# ptSolar.net
KiCad netlist of a schematic drawn in EAGLE
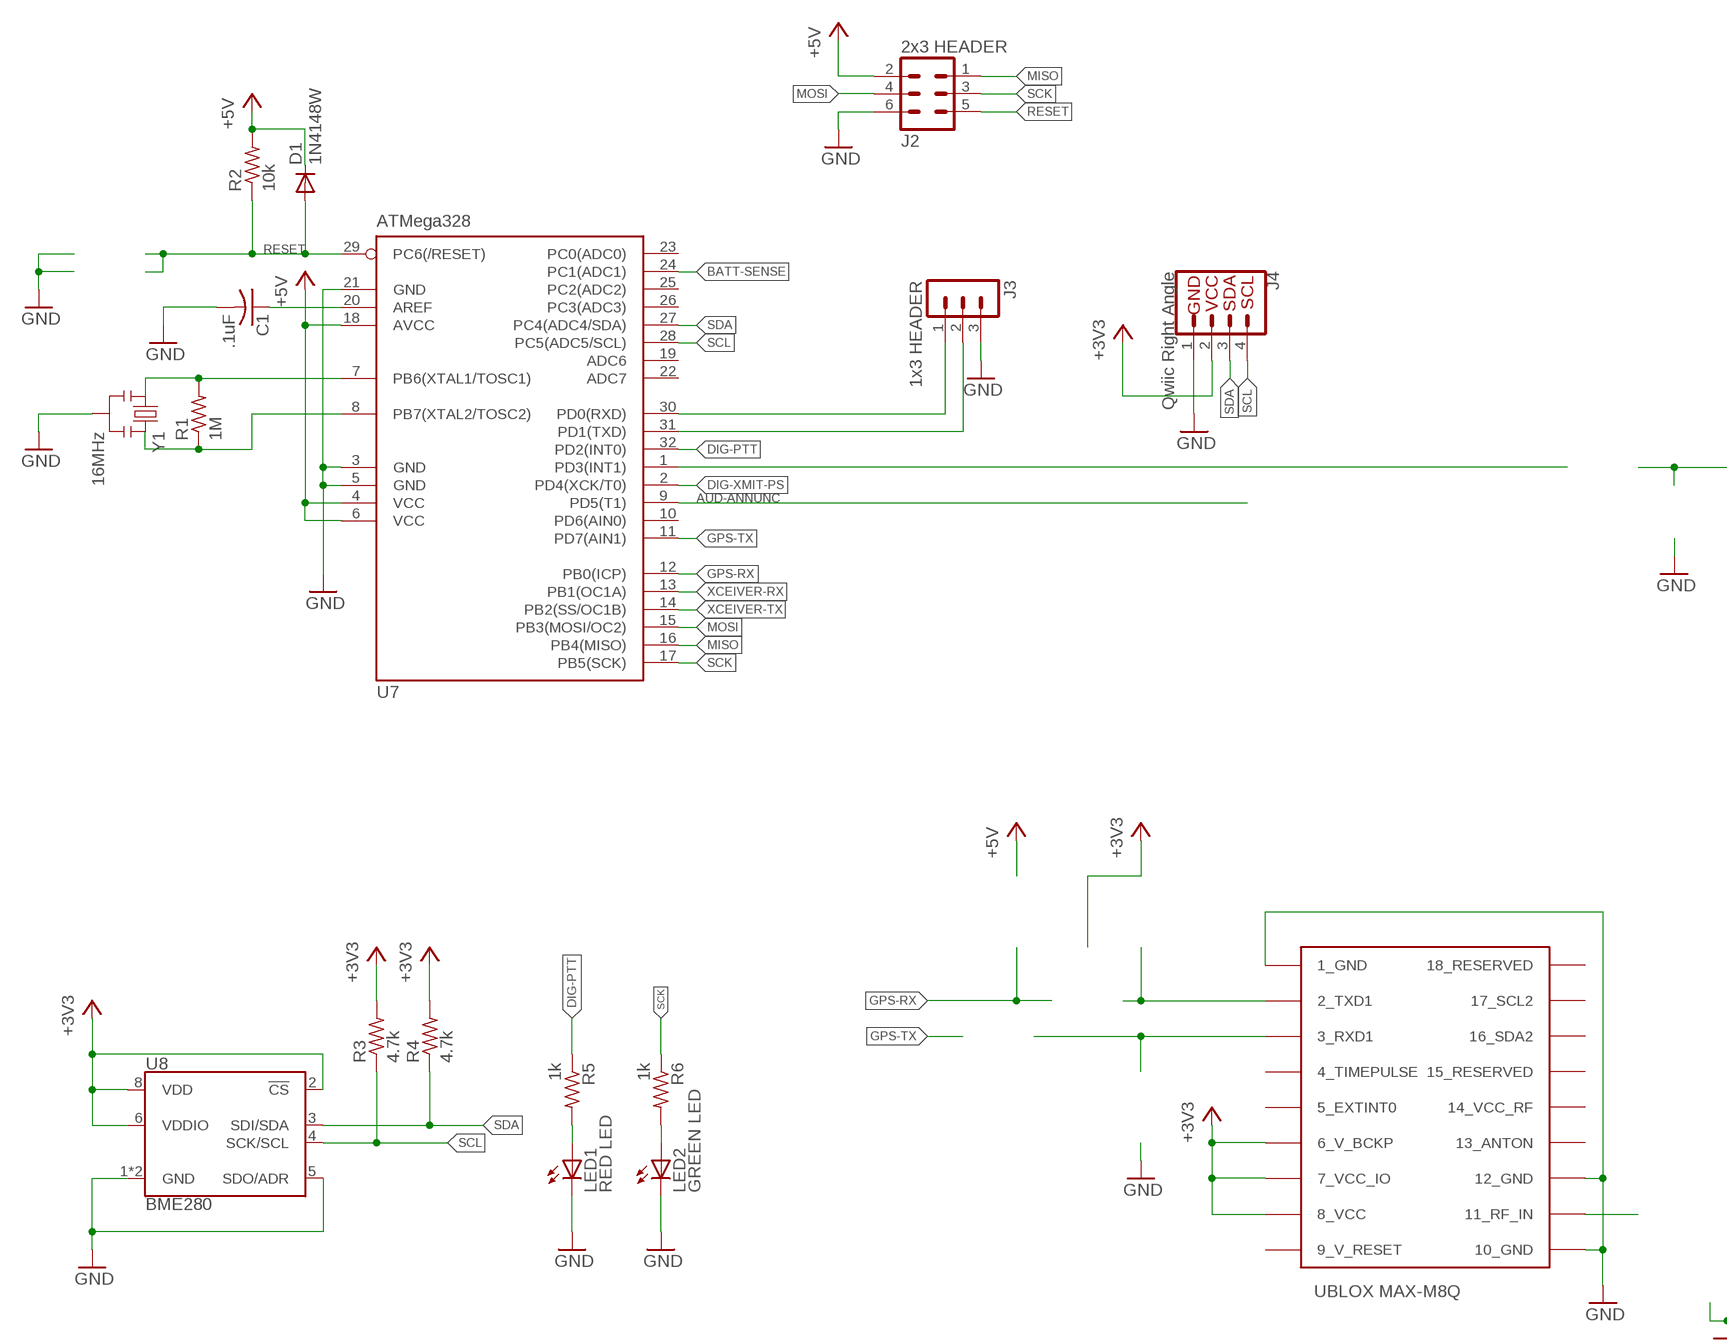
[diagram p0: schematic, sheet 1, part 1 of 2]
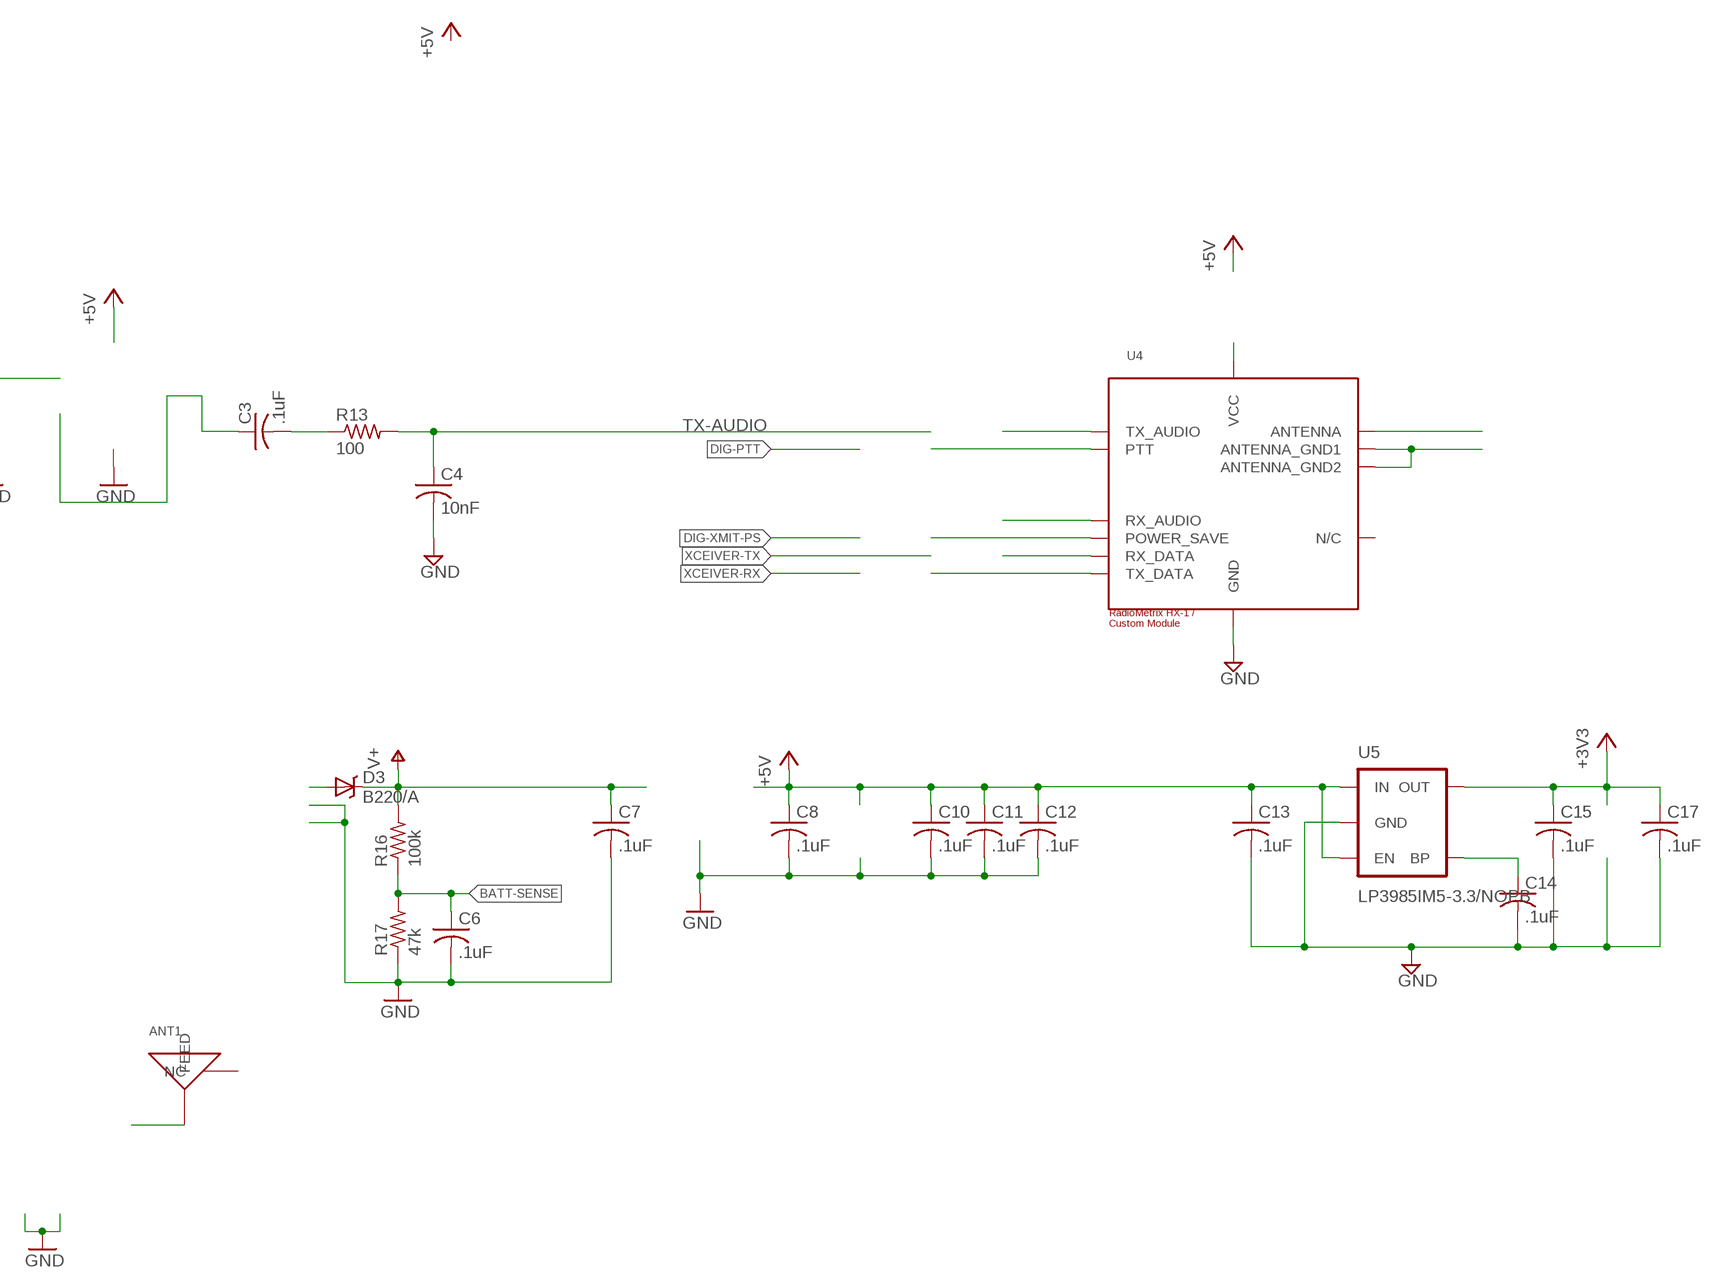
[diagram p1: schematic, sheet 1, part 2 of 2]

(export (version "E")
  (design (tool "Eeschema 10.0.6"))
  (components
    (comp (ref "ANT1")
      (value "GPS ANTENNA")
      (footprint "eagle-import:1575AT43A40")
      (libsource (lib "eagle-import") (part "GPS_ANT_SMDBAR"))
    )
    (comp (ref "C1")
      (value ".1uF")
      (footprint "eagle-import:C0805")
      (libsource (lib "eagle-import") (part "C-USC0805"))
    )
    (comp (ref "C3")
      (value ".1uF")
      (footprint "eagle-import:C0805")
      (libsource (lib "eagle-import") (part "C-USC0805"))
    )
    (comp (ref "C4")
      (value "10nF")
      (footprint "eagle-import:C0805")
      (libsource (lib "eagle-import") (part "C-USC0805"))
    )
    (comp (ref "C6")
      (value ".1uF")
      (footprint "eagle-import:C0805")
      (libsource (lib "eagle-import") (part "C-USC0805"))
    )
    (comp (ref "C7")
      (value ".1uF")
      (footprint "eagle-import:C0805")
      (libsource (lib "eagle-import") (part "C-USC0805"))
    )
    (comp (ref "C8")
      (value ".1uF")
      (footprint "eagle-import:C0805")
      (libsource (lib "eagle-import") (part "C-USC0805"))
    )
    (comp (ref "C10")
      (value ".1uF")
      (footprint "eagle-import:C0805")
      (libsource (lib "eagle-import") (part "C-USC0805"))
    )
    (comp (ref "C11")
      (value ".1uF")
      (footprint "eagle-import:C0805")
      (libsource (lib "eagle-import") (part "C-USC0805"))
    )
    (comp (ref "C12")
      (value ".1uF")
      (footprint "eagle-import:C0805")
      (libsource (lib "eagle-import") (part "C-USC0805"))
    )
    (comp (ref "C13")
      (value ".1uF")
      (footprint "eagle-import:C0805")
      (libsource (lib "eagle-import") (part "C-USC0805"))
    )
    (comp (ref "C14")
      (value ".1uF")
      (footprint "eagle-import:C0805")
      (libsource (lib "eagle-import") (part "C-USC0805"))
    )
    (comp (ref "C15")
      (value ".1uF")
      (footprint "eagle-import:C0805")
      (libsource (lib "eagle-import") (part "C-USC0805"))
    )
    (comp (ref "C17")
      (value ".1uF")
      (footprint "eagle-import:C0805")
      (libsource (lib "eagle-import") (part "C-USC0805"))
    )
    (comp (ref "D1")
      (value "1N4148W")
      (footprint "eagle-import:SOD123")
      (libsource (lib "eagle-import") (part "DIODE-SOD123"))
    )
    (comp (ref "D3")
      (value "B220/A")
      (footprint "eagle-import:SMA-DIODE")
      (libsource (lib "eagle-import") (part "B340A"))
    )
    (comp (ref "J2")
      (value "2x3 HEADER")
      (footprint "eagle-import:MA03-2")
      (libsource (lib "eagle-import") (part "MA03-2"))
    )
    (comp (ref "J3")
      (value "1x3 HEADER")
      (footprint "eagle-import:MA03-1")
      (libsource (lib "eagle-import") (part "MA03-1"))
    )
    (comp (ref "J4")
      (value "Qwiic Right Angle")
      (footprint "eagle-import:1X04_1MM_RA")
      (libsource (lib "eagle-import") (part "I2C_STANDARDQWIIC"))
    )
    (comp (ref "LED1")
      (value "RED LED")
      (footprint "eagle-import:CHIPLED_1206")
      (libsource (lib "eagle-import") (part "LEDCHIPLED_1206"))
    )
    (comp (ref "LED2")
      (value "GREEN LED")
      (footprint "eagle-import:CHIPLED_1206")
      (libsource (lib "eagle-import") (part "LEDCHIPLED_1206"))
    )
    (comp (ref "R1")
      (value "1M")
      (footprint "eagle-import:R0805")
      (libsource (lib "eagle-import") (part "R-US_R0805"))
    )
    (comp (ref "R2")
      (value "10k")
      (footprint "eagle-import:R0805")
      (libsource (lib "eagle-import") (part "R-US_R0805"))
    )
    (comp (ref "R3")
      (value "4.7k")
      (footprint "eagle-import:R0805")
      (libsource (lib "eagle-import") (part "R-US_R0805"))
    )
    (comp (ref "R4")
      (value "4.7k")
      (footprint "eagle-import:R0805")
      (libsource (lib "eagle-import") (part "R-US_R0805"))
    )
    (comp (ref "R5")
      (value "1k")
      (footprint "eagle-import:R0805")
      (libsource (lib "eagle-import") (part "R-US_R0805"))
    )
    (comp (ref "R6")
      (value "1k")
      (footprint "eagle-import:R0805")
      (libsource (lib "eagle-import") (part "R-US_R0805"))
    )
    (comp (ref "R13")
      (value "100")
      (footprint "eagle-import:R0805")
      (libsource (lib "eagle-import") (part "R-US_R0805"))
    )
    (comp (ref "R16")
      (value "100k")
      (footprint "eagle-import:R0805")
      (libsource (lib "eagle-import") (part "R-US_R0805"))
    )
    (comp (ref "R17")
      (value "47k")
      (footprint "eagle-import:R0805")
      (libsource (lib "eagle-import") (part "R-US_R0805"))
    )
    (comp (ref "U2")
      (value "UBLOX_MAX")
      (footprint "eagle-import:UBLOX_MAX")
      (fields (field (name "ALT-PART") "UBLOX MAX-M8Q"))
      (libsource (lib "eagle-import") (part "UBLOX_MAX"))
    )
    (comp (ref "U4")
      (value "RADIOMETRIX-HX1-CUSTOM")
      (footprint "eagle-import:RADIOMETRIX-HX1-CUSTOM")
      (libsource (lib "eagle-import") (part "RADIOMETRIX-HX1-CUSTOM"))
    )
    (comp (ref "U5")
      (value "LP3985IM5-3.3/NOPB")
      (footprint "eagle-import:SOT23-5")
      (libsource (lib "eagle-import") (part "V_REG_LDOSMD"))
    )
    (comp (ref "U7")
      (value "ATMega328")
      (footprint "eagle-import:TQFP32-08")
      (fields (field (name "MPN") "ATMEGA8-16AU"))
      (libsource (lib "eagle-import") (part "MEGA8-AI"))
    )
    (comp (ref "U8")
      (value "BME280")
      (footprint "eagle-import:LGA-8-2.5X2.5")
      (libsource (lib "eagle-import") (part "BME280"))
    )
    (comp (ref "Y1")
      (value "16MHz")
      (footprint "eagle-import:RESONATOR-SMD")
      (libsource (lib "eagle-import") (part "RESONATOR16MHZ"))
    )
  )
  (nets
    (net (code "1") (name "+3V3") (class "Default")
      (node (ref "C15") (pin "1") (pinfunction "1_1") (pintype "passive"))
      (node (ref "C17") (pin "1") (pinfunction "1_1") (pintype "passive"))
      (node (ref "J4") (pin "2") (pinfunction "2_2") (pintype "power_in"))
      (node (ref "R3") (pin "2") (pinfunction "2_2") (pintype "passive"))
      (node (ref "R4") (pin "2") (pinfunction "2_2") (pintype "passive"))
      (node (ref "U2") (pin "6_V_BCKP") (pinfunction "6_V_BCKP_6_V_BCKP") (pintype "bidirectional"))
      (node (ref "U2") (pin "7_VCC_IO") (pinfunction "7_VCC_IO_7_VCC_IO") (pintype "power_in"))
      (node (ref "U2") (pin "8_VCC") (pinfunction "8_VCC_8_VCC") (pintype "power_in"))
      (node (ref "U5") (pin "5") (pinfunction "OUT_5") (pintype "passive"))
      (node (ref "U8") (pin "2") (pinfunction "~{CS}_2") (pintype "bidirectional"))
      (node (ref "U8") (pin "6") (pinfunction "VDDIO_6") (pintype "bidirectional"))
      (node (ref "U8") (pin "8") (pinfunction "VDD_8") (pintype "bidirectional"))
    )
    (net (code "2") (name "+5V") (class "Default")
      (node (ref "C10") (pin "1") (pinfunction "1_1") (pintype "passive"))
      (node (ref "C11") (pin "1") (pinfunction "1_1") (pintype "passive"))
      (node (ref "C12") (pin "1") (pinfunction "1_1") (pintype "passive"))
      (node (ref "C13") (pin "1") (pinfunction "1_1") (pintype "passive"))
      (node (ref "C8") (pin "1") (pinfunction "1_1") (pintype "passive"))
      (node (ref "D1") (pin "C") (pinfunction "C_C") (pintype "passive"))
      (node (ref "J2") (pin "2") (pinfunction "2_2") (pintype "passive"))
      (node (ref "R2") (pin "2") (pinfunction "2_2") (pintype "passive"))
      (node (ref "U5") (pin "1") (pinfunction "IN_1") (pintype "input"))
      (node (ref "U5") (pin "3") (pinfunction "EN_3") (pintype "input"))
      (node (ref "U7") (pin "18") (pinfunction "AVCC_18") (pintype "power_in"))
      (node (ref "U7") (pin "4") (pinfunction "VCC_4") (pintype "power_in"))
      (node (ref "U7") (pin "6") (pinfunction "VCC_6") (pintype "power_in"))
    )
    (net (code "3") (name "/9_V_RESET") (class "Default")
      (node (ref "U2") (pin "9_V_RESET") (pinfunction "9_V_RESET_9_V_RESET") (pintype "power_in"))
    )
    (net (code "4") (name "/AUD-ANNUNC") (class "Default")
      (node (ref "U7") (pin "9") (pinfunction "PD5(T1)_9") (pintype "bidirectional"))
    )
    (net (code "5") (name "/TX-AUDIO") (class "Default")
      (node (ref "C3") (pin "2") (pinfunction "2_2") (pintype "passive"))
      (node (ref "R13") (pin "1") (pinfunction "1_1") (pintype "passive"))
    )
    (net (code "6") (name "BATT-SENSE") (class "Default")
      (node (ref "C6") (pin "1") (pinfunction "1_1") (pintype "passive"))
      (node (ref "R16") (pin "1") (pinfunction "1_1") (pintype "passive"))
      (node (ref "R17") (pin "2") (pinfunction "2_2") (pintype "passive"))
      (node (ref "U7") (pin "24") (pinfunction "PC1(ADC1)_24") (pintype "bidirectional"))
    )
    (net (code "7") (name "DIG-PTT") (class "Default")
      (node (ref "R5") (pin "1") (pinfunction "1_1") (pintype "passive"))
      (node (ref "U7") (pin "32") (pinfunction "PD2(INT0)_32") (pintype "bidirectional"))
    )
    (net (code "8") (name "DIG-XMIT-PS") (class "Default")
      (node (ref "U7") (pin "2") (pinfunction "PD4(XCK/T0)_2") (pintype "bidirectional"))
    )
    (net (code "9") (name "GND") (class "Default")
      (node (ref "C1") (pin "2") (pinfunction "2_2") (pintype "passive"))
      (node (ref "C10") (pin "2") (pinfunction "2_2") (pintype "passive"))
      (node (ref "C11") (pin "2") (pinfunction "2_2") (pintype "passive"))
      (node (ref "C12") (pin "2") (pinfunction "2_2") (pintype "passive"))
      (node (ref "C13") (pin "2") (pinfunction "2_2") (pintype "passive"))
      (node (ref "C14") (pin "2") (pinfunction "2_2") (pintype "passive"))
      (node (ref "C15") (pin "2") (pinfunction "2_2") (pintype "passive"))
      (node (ref "C17") (pin "2") (pinfunction "2_2") (pintype "passive"))
      (node (ref "C4") (pin "2") (pinfunction "2_2") (pintype "passive"))
      (node (ref "C6") (pin "2") (pinfunction "2_2") (pintype "passive"))
      (node (ref "C7") (pin "2") (pinfunction "2_2") (pintype "passive"))
      (node (ref "C8") (pin "2") (pinfunction "2_2") (pintype "passive"))
      (node (ref "J2") (pin "6") (pinfunction "6_6") (pintype "passive"))
      (node (ref "J3") (pin "3") (pinfunction "3_3") (pintype "passive"))
      (node (ref "J4") (pin "1") (pinfunction "1_1") (pintype "power_in"))
      (node (ref "LED1") (pin "C") (pinfunction "C_C") (pintype "passive"))
      (node (ref "LED2") (pin "C") (pinfunction "C_C") (pintype "passive"))
      (node (ref "R17") (pin "1") (pinfunction "1_1") (pintype "passive"))
      (node (ref "U2") (pin "10_GND") (pinfunction "10_GND_10_GND") (pintype "power_in"))
      (node (ref "U2") (pin "12_GND") (pinfunction "12_GND_12_GND") (pintype "power_in"))
      (node (ref "U2") (pin "1_GND") (pinfunction "1_GND_1_GND") (pintype "power_in"))
      (node (ref "U4") (pin "GND") (pinfunction "GND_GND") (pintype "power_in"))
      (node (ref "U5") (pin "2") (pinfunction "GND_2") (pintype "input"))
      (node (ref "U7") (pin "21") (pinfunction "GND_21") (pintype "power_in"))
      (node (ref "U7") (pin "3") (pinfunction "GND_3") (pintype "power_in"))
      (node (ref "U7") (pin "5") (pinfunction "GND_5") (pintype "power_in"))
      (node (ref "U8") (pin "1") (pinfunction "GND_1") (pintype "bidirectional"))
      (node (ref "U8") (pin "5") (pinfunction "SDO/ADR_5") (pintype "bidirectional"))
      (node (ref "U8") (pin "7") (pinfunction "GND_7") (pintype "bidirectional"))
      (node (ref "Y1") (pin "2") (pinfunction "2_2") (pintype "passive"))
    )
    (net (code "10") (name "GPS-RX") (class "Default")
      (node (ref "U7") (pin "12") (pinfunction "PB0(ICP)_12") (pintype "bidirectional"))
    )
    (net (code "11") (name "GPS-TX") (class "Default")
      (node (ref "U7") (pin "11") (pinfunction "PD7(AIN1)_11") (pintype "bidirectional"))
    )
    (net (code "12") (name "MISO") (class "Default")
      (node (ref "J2") (pin "1") (pinfunction "1_1") (pintype "passive"))
      (node (ref "U7") (pin "16") (pinfunction "PB4(MISO)_16") (pintype "bidirectional"))
    )
    (net (code "13") (name "MOSI") (class "Default")
      (node (ref "J2") (pin "4") (pinfunction "4_4") (pintype "passive"))
      (node (ref "U7") (pin "15") (pinfunction "PB3(MOSI/OC2)_15") (pintype "bidirectional"))
    )
    (net (code "14") (name "Net-(C4-Pad1)") (class "Default")
      (node (ref "C4") (pin "1") (pinfunction "1_1") (pintype "passive"))
      (node (ref "R13") (pin "2") (pinfunction "2_2") (pintype "passive"))
    )
    (net (code "15") (name "Net-(LED1-PadA)") (class "Default")
      (node (ref "LED1") (pin "A") (pinfunction "A_A") (pintype "passive"))
      (node (ref "R5") (pin "2") (pinfunction "2_2") (pintype "passive"))
    )
    (net (code "16") (name "Net-(LED2-PadA)") (class "Default")
      (node (ref "LED2") (pin "A") (pinfunction "A_A") (pintype "passive"))
      (node (ref "R6") (pin "2") (pinfunction "2_2") (pintype "passive"))
    )
    (net (code "17") (name "Net-(U4-PadANTENNA_GND1)") (class "Default")
      (node (ref "U4") (pin "ANTENNA_GND1") (pinfunction "ANTENNA_GND1_ANTENNA_GND1") (pintype "bidirectional"))
      (node (ref "U4") (pin "ANTENNA_GND2") (pinfunction "ANTENNA_GND2_ANTENNA_GND2") (pintype "bidirectional"))
    )
    (net (code "18") (name "Net-(U5-BP)") (class "Default")
      (node (ref "C14") (pin "1") (pinfunction "1_1") (pintype "passive"))
      (node (ref "U5") (pin "4") (pinfunction "BP_4") (pintype "input"))
    )
    (net (code "19") (name "Net-(U7-AREF)") (class "Default")
      (node (ref "C1") (pin "1") (pinfunction "1_1") (pintype "passive"))
      (node (ref "U7") (pin "20") (pinfunction "AREF_20") (pintype "passive"))
    )
    (net (code "20") (name "Net-(U7-PB6(XTAL1{slash}TOSC1))") (class "Default")
      (node (ref "R1") (pin "2") (pinfunction "2_2") (pintype "passive"))
      (node (ref "U7") (pin "7") (pinfunction "PB6(XTAL1/TOSC1)_7") (pintype "bidirectional"))
      (node (ref "Y1") (pin "1") (pinfunction "1_1") (pintype "passive"))
    )
    (net (code "21") (name "Net-(U7-PB7(XTAL2{slash}TOSC2))") (class "Default")
      (node (ref "R1") (pin "1") (pinfunction "1_1") (pintype "passive"))
      (node (ref "U7") (pin "8") (pinfunction "PB7(XTAL2/TOSC2)_8") (pintype "bidirectional"))
      (node (ref "Y1") (pin "3") (pinfunction "3_3") (pintype "passive"))
    )
    (net (code "22") (name "Net-(U7-PD0(RXD))") (class "Default")
      (node (ref "J3") (pin "1") (pinfunction "1_1") (pintype "passive"))
      (node (ref "U7") (pin "30") (pinfunction "PD0(RXD)_30") (pintype "bidirectional"))
    )
    (net (code "23") (name "Net-(U7-PD1(TXD))") (class "Default")
      (node (ref "J3") (pin "2") (pinfunction "2_2") (pintype "passive"))
      (node (ref "U7") (pin "31") (pinfunction "PD1(TXD)_31") (pintype "bidirectional"))
    )
    (net (code "24") (name "RESET") (class "Default")
      (node (ref "D1") (pin "A") (pinfunction "A_A") (pintype "passive"))
      (node (ref "J2") (pin "5") (pinfunction "5_5") (pintype "passive"))
      (node (ref "R2") (pin "1") (pinfunction "1_1") (pintype "passive"))
      (node (ref "U7") (pin "29") (pinfunction "PC6(/RESET)_29") (pintype "bidirectional"))
    )
    (net (code "25") (name "SCK") (class "Default")
      (node (ref "J2") (pin "3") (pinfunction "3_3") (pintype "passive"))
      (node (ref "R6") (pin "1") (pinfunction "1_1") (pintype "passive"))
      (node (ref "U7") (pin "17") (pinfunction "PB5(SCK)_17") (pintype "bidirectional"))
    )
    (net (code "26") (name "SCL") (class "Default")
      (node (ref "J4") (pin "4") (pinfunction "4_4") (pintype "passive"))
      (node (ref "R3") (pin "1") (pinfunction "1_1") (pintype "passive"))
      (node (ref "U7") (pin "28") (pinfunction "PC5(ADC5/SCL)_28") (pintype "bidirectional"))
      (node (ref "U8") (pin "4") (pinfunction "SCK/SCL_4") (pintype "bidirectional"))
    )
    (net (code "27") (name "SDA") (class "Default")
      (node (ref "J4") (pin "3") (pinfunction "3_3") (pintype "passive"))
      (node (ref "R4") (pin "1") (pinfunction "1_1") (pintype "passive"))
      (node (ref "U7") (pin "27") (pinfunction "PC4(ADC4/SDA)_27") (pintype "bidirectional"))
      (node (ref "U8") (pin "3") (pinfunction "SDI/SDA_3") (pintype "bidirectional"))
    )
    (net (code "28") (name "V+") (class "Default")
      (node (ref "C7") (pin "1") (pinfunction "1_1") (pintype "passive"))
      (node (ref "D3") (pin "C") (pinfunction "C_C") (pintype "passive"))
      (node (ref "R16") (pin "2") (pinfunction "2_2") (pintype "passive"))
    )
    (net (code "29") (name "XCEIVER-RX") (class "Default")
      (node (ref "U7") (pin "13") (pinfunction "PB1(OC1A)_13") (pintype "bidirectional"))
    )
    (net (code "30") (name "XCEIVER-TX") (class "Default")
      (node (ref "U7") (pin "14") (pinfunction "PB2(SS/OC1B)_14") (pintype "bidirectional"))
    )
    (net (code "31") (name "unconnected-(ANT1-PadFEED)") (class "Default")
      (node (ref "ANT1") (pin "FEED") (pinfunction "FEED_FEED") (pintype "bidirectional"))
    )
    (net (code "32") (name "unconnected-(ANT1-PadNC)") (class "Default")
      (node (ref "ANT1") (pin "NC") (pinfunction "NC_NC") (pintype "bidirectional"))
    )
    (net (code "33") (name "unconnected-(C3-Pad1)") (class "Default")
      (node (ref "C3") (pin "1") (pinfunction "1_1") (pintype "passive"))
    )
    (net (code "34") (name "unconnected-(D3-PadA)") (class "Default")
      (node (ref "D3") (pin "A") (pinfunction "A_A") (pintype "passive"))
    )
    (net (code "35") (name "unconnected-(U2-Pad2_TXD1)") (class "Default")
      (node (ref "U2") (pin "2_TXD1") (pinfunction "2_TXD1_2_TXD1") (pintype "bidirectional"))
    )
    (net (code "36") (name "unconnected-(U2-Pad3_RXD1)") (class "Default")
      (node (ref "U2") (pin "3_RXD1") (pinfunction "3_RXD1_3_RXD1") (pintype "bidirectional"))
    )
    (net (code "37") (name "unconnected-(U2-Pad4_TIMEPULSE)") (class "Default")
      (node (ref "U2") (pin "4_TIMEPULSE") (pinfunction "4_TIMEPULSE_4_TIMEPULSE") (pintype "bidirectional"))
    )
    (net (code "38") (name "unconnected-(U2-Pad5_EXTINT0)") (class "Default")
      (node (ref "U2") (pin "5_EXTINT0") (pinfunction "5_EXTINT0_5_EXTINT0") (pintype "bidirectional"))
    )
    (net (code "39") (name "unconnected-(U2-Pad11_RF_IN)") (class "Default")
      (node (ref "U2") (pin "11_RF_IN") (pinfunction "11_RF_IN_11_RF_IN") (pintype "bidirectional"))
    )
    (net (code "40") (name "unconnected-(U2-Pad13_ANTON)") (class "Default")
      (node (ref "U2") (pin "13_ANTON") (pinfunction "13_ANTON_13_ANTON") (pintype "bidirectional"))
    )
    (net (code "41") (name "unconnected-(U2-Pad14_VCC_RF)") (class "Default")
      (node (ref "U2") (pin "14_VCC_RF") (pinfunction "14_VCC_RF_14_VCC_RF") (pintype "bidirectional"))
    )
    (net (code "42") (name "unconnected-(U2-Pad15_RESERVED)") (class "Default")
      (node (ref "U2") (pin "15_RESERVED") (pinfunction "15_RESERVED_15_RESERVED") (pintype "bidirectional"))
    )
    (net (code "43") (name "unconnected-(U2-Pad16_SDA2)") (class "Default")
      (node (ref "U2") (pin "16_SDA2") (pinfunction "16_SDA2_16_SDA2") (pintype "bidirectional"))
    )
    (net (code "44") (name "unconnected-(U2-Pad17_SCL2)") (class "Default")
      (node (ref "U2") (pin "17_SCL2") (pinfunction "17_SCL2_17_SCL2") (pintype "bidirectional"))
    )
    (net (code "45") (name "unconnected-(U2-Pad18_RESERVED)") (class "Default")
      (node (ref "U2") (pin "18_RESERVED") (pinfunction "18_RESERVED_18_RESERVED") (pintype "bidirectional"))
    )
    (net (code "46") (name "unconnected-(U4-N{slash}C-PadN{slash}C1)") (class "Default")
      (node (ref "U4") (pin "N/C1") (pinfunction "N/C_N/C1") (pintype "no_connect"))
    )
    (net (code "47") (name "unconnected-(U4-N{slash}C-PadN{slash}C2)") (class "Default")
      (node (ref "U4") (pin "N/C2") (pinfunction "N/C_N/C2") (pintype "no_connect"))
    )
    (net (code "48") (name "unconnected-(U4-N{slash}C-PadN{slash}C3)") (class "Default")
      (node (ref "U4") (pin "N/C3") (pinfunction "N/C_N/C3") (pintype "no_connect"))
    )
    (net (code "49") (name "unconnected-(U4-N{slash}C-PadN{slash}C4)") (class "Default")
      (node (ref "U4") (pin "N/C4") (pinfunction "N/C_N/C4") (pintype "no_connect"))
    )
    (net (code "50") (name "unconnected-(U4-PadANTENNA)") (class "Default")
      (node (ref "U4") (pin "ANTENNA") (pinfunction "ANTENNA_ANTENNA") (pintype "bidirectional"))
    )
    (net (code "51") (name "unconnected-(U4-PadPOWER_SAVE)") (class "Default")
      (node (ref "U4") (pin "POWER_SAVE") (pinfunction "POWER_SAVE_POWER_SAVE") (pintype "input"))
    )
    (net (code "52") (name "unconnected-(U4-PadPTT)") (class "Default")
      (node (ref "U4") (pin "PTT") (pinfunction "PTT_PTT") (pintype "input"))
    )
    (net (code "53") (name "unconnected-(U4-PadRX_AUDIO)") (class "Default")
      (node (ref "U4") (pin "RX_AUDIO") (pinfunction "RX_AUDIO_RX_AUDIO") (pintype "output"))
    )
    (net (code "54") (name "unconnected-(U4-PadRX_DATA)") (class "Default")
      (node (ref "U4") (pin "RX_DATA") (pinfunction "RX_DATA_RX_DATA") (pintype "input"))
    )
    (net (code "55") (name "unconnected-(U4-PadTX_AUDIO)") (class "Default")
      (node (ref "U4") (pin "TX_AUDIO") (pinfunction "TX_AUDIO_TX_AUDIO") (pintype "input"))
    )
    (net (code "56") (name "unconnected-(U4-PadTX_DATA)") (class "Default")
      (node (ref "U4") (pin "TX_DATA") (pinfunction "TX_DATA_TX_DATA") (pintype "output"))
    )
    (net (code "57") (name "unconnected-(U4-PadVCC)") (class "Default")
      (node (ref "U4") (pin "VCC") (pinfunction "VCC_VCC") (pintype "power_in"))
    )
    (net (code "58") (name "unconnected-(U7-ADC6-Pad19)") (class "Default")
      (node (ref "U7") (pin "19") (pinfunction "ADC6_19") (pintype "bidirectional"))
    )
    (net (code "59") (name "unconnected-(U7-ADC7-Pad22)") (class "Default")
      (node (ref "U7") (pin "22") (pinfunction "ADC7_22") (pintype "bidirectional"))
    )
    (net (code "60") (name "unconnected-(U7-PC0(ADC0)-Pad23)") (class "Default")
      (node (ref "U7") (pin "23") (pinfunction "PC0(ADC0)_23") (pintype "bidirectional"))
    )
    (net (code "61") (name "unconnected-(U7-PC2(ADC2)-Pad25)") (class "Default")
      (node (ref "U7") (pin "25") (pinfunction "PC2(ADC2)_25") (pintype "bidirectional"))
    )
    (net (code "62") (name "unconnected-(U7-PC3(ADC3)-Pad26)") (class "Default")
      (node (ref "U7") (pin "26") (pinfunction "PC3(ADC3)_26") (pintype "bidirectional"))
    )
    (net (code "63") (name "unconnected-(U7-PD3(INT1)-Pad1)") (class "Default")
      (node (ref "U7") (pin "1") (pinfunction "PD3(INT1)_1") (pintype "bidirectional"))
    )
    (net (code "64") (name "unconnected-(U7-PD6(AIN0)-Pad10)") (class "Default")
      (node (ref "U7") (pin "10") (pinfunction "PD6(AIN0)_10") (pintype "bidirectional"))
    )
  )
)
